# PatchPanel.net
KiCad netlist of a schematic drawn in EAGLE
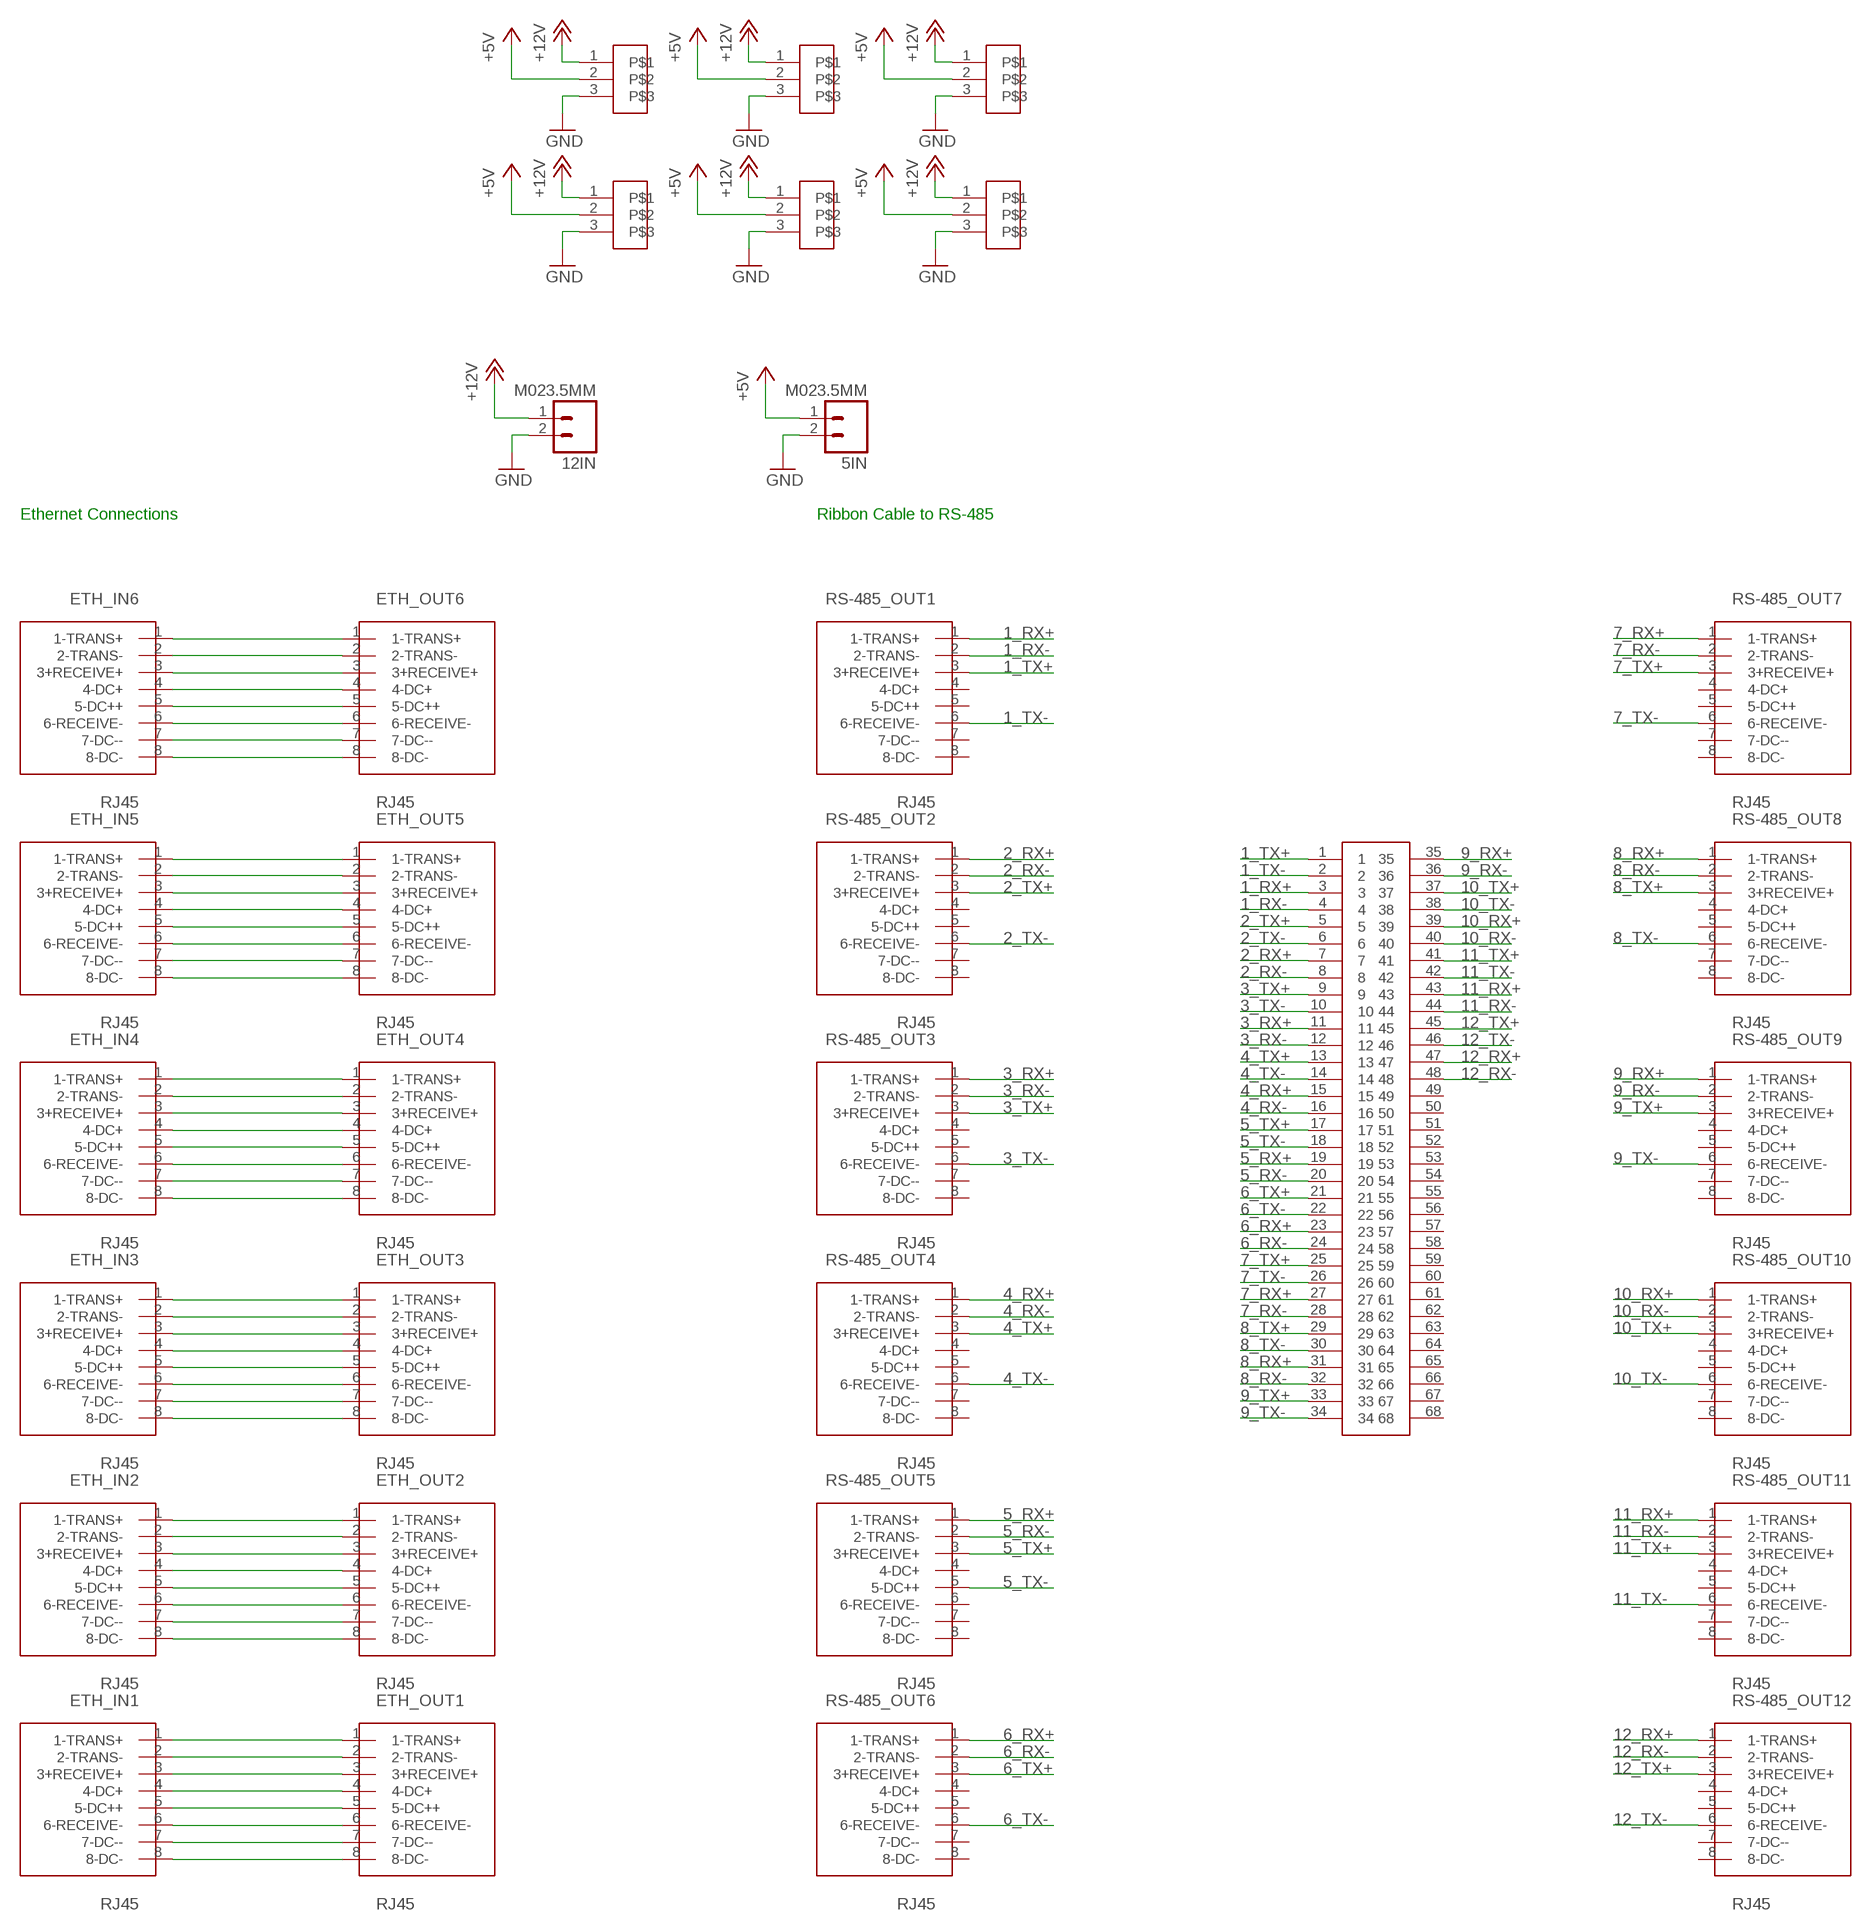
[diagram p0: schematic, sheet 1]

(export (version "E")
  (design (tool "Eeschema 10.0.6"))
  (components
    (comp (ref "5IN")
      (value "M023.5MM")
      (footprint "eagle-import:SCREWTERMINAL-3.5MM-2")
      (libsource (lib "eagle-import") (part "M023.5MM"))
    )
    (comp (ref "12IN")
      (value "M023.5MM")
      (footprint "eagle-import:SCREWTERMINAL-3.5MM-2")
      (libsource (lib "eagle-import") (part "M023.5MM"))
    )
    (comp (ref "ETH_IN1")
      (value "RJ45")
      (footprint "eagle-import:RJ45-CAT5E")
      (libsource (lib "eagle-import") (part "RJ45"))
    )
    (comp (ref "ETH_IN2")
      (value "RJ45")
      (footprint "eagle-import:RJ45-CAT5E")
      (libsource (lib "eagle-import") (part "RJ45"))
    )
    (comp (ref "ETH_IN3")
      (value "RJ45")
      (footprint "eagle-import:RJ45-CAT5E")
      (libsource (lib "eagle-import") (part "RJ45"))
    )
    (comp (ref "ETH_IN4")
      (value "RJ45")
      (footprint "eagle-import:RJ45-CAT5E")
      (libsource (lib "eagle-import") (part "RJ45"))
    )
    (comp (ref "ETH_IN5")
      (value "RJ45")
      (footprint "eagle-import:RJ45-CAT5E")
      (libsource (lib "eagle-import") (part "RJ45"))
    )
    (comp (ref "ETH_IN6")
      (value "RJ45")
      (footprint "eagle-import:RJ45-CAT5E")
      (libsource (lib "eagle-import") (part "RJ45"))
    )
    (comp (ref "ETH_OUT1")
      (value "RJ45")
      (footprint "eagle-import:RJ45-CAT5E")
      (libsource (lib "eagle-import") (part "RJ45"))
    )
    (comp (ref "ETH_OUT2")
      (value "RJ45")
      (footprint "eagle-import:RJ45-CAT5E")
      (libsource (lib "eagle-import") (part "RJ45"))
    )
    (comp (ref "ETH_OUT3")
      (value "RJ45")
      (footprint "eagle-import:RJ45-CAT5E")
      (libsource (lib "eagle-import") (part "RJ45"))
    )
    (comp (ref "ETH_OUT4")
      (value "RJ45")
      (footprint "eagle-import:RJ45-CAT5E")
      (libsource (lib "eagle-import") (part "RJ45"))
    )
    (comp (ref "ETH_OUT5")
      (value "RJ45")
      (footprint "eagle-import:RJ45-CAT5E")
      (libsource (lib "eagle-import") (part "RJ45"))
    )
    (comp (ref "ETH_OUT6")
      (value "RJ45")
      (footprint "eagle-import:RJ45-CAT5E")
      (libsource (lib "eagle-import") (part "RJ45"))
    )
    (comp (ref "RS-485_OUT1")
      (value "RJ45")
      (footprint "eagle-import:RJ45-CAT5E")
      (libsource (lib "eagle-import") (part "RJ45"))
    )
    (comp (ref "RS-485_OUT2")
      (value "RJ45")
      (footprint "eagle-import:RJ45-CAT5E")
      (libsource (lib "eagle-import") (part "RJ45"))
    )
    (comp (ref "RS-485_OUT3")
      (value "RJ45")
      (footprint "eagle-import:RJ45-CAT5E")
      (libsource (lib "eagle-import") (part "RJ45"))
    )
    (comp (ref "RS-485_OUT4")
      (value "RJ45")
      (footprint "eagle-import:RJ45-CAT5E")
      (libsource (lib "eagle-import") (part "RJ45"))
    )
    (comp (ref "RS-485_OUT5")
      (value "RJ45")
      (footprint "eagle-import:RJ45-CAT5E")
      (libsource (lib "eagle-import") (part "RJ45"))
    )
    (comp (ref "RS-485_OUT6")
      (value "RJ45")
      (footprint "eagle-import:RJ45-CAT5E")
      (libsource (lib "eagle-import") (part "RJ45"))
    )
    (comp (ref "RS-485_OUT7")
      (value "RJ45")
      (footprint "eagle-import:RJ45-CAT5E")
      (libsource (lib "eagle-import") (part "RJ45"))
    )
    (comp (ref "RS-485_OUT8")
      (value "RJ45")
      (footprint "eagle-import:RJ45-CAT5E")
      (libsource (lib "eagle-import") (part "RJ45"))
    )
    (comp (ref "RS-485_OUT9")
      (value "RJ45")
      (footprint "eagle-import:RJ45-CAT5E")
      (libsource (lib "eagle-import") (part "RJ45"))
    )
    (comp (ref "RS-485_OUT10")
      (value "RJ45")
      (footprint "eagle-import:RJ45-CAT5E")
      (libsource (lib "eagle-import") (part "RJ45"))
    )
    (comp (ref "RS-485_OUT11")
      (value "RJ45")
      (footprint "eagle-import:RJ45-CAT5E")
      (libsource (lib "eagle-import") (part "RJ45"))
    )
    (comp (ref "RS-485_OUT12")
      (value "RJ45")
      (footprint "eagle-import:RJ45-CAT5E")
      (libsource (lib "eagle-import") (part "RJ45"))
    )
    (comp (ref "U$1")
      (value "TB60050685100")
      (footprint "eagle-import:60050685100")
      (libsource (lib "eagle-import") (part "TB60050685100"))
    )
    (comp (ref "U$2")
      (value "3PIN")
      (footprint "eagle-import:0.93_")
      (libsource (lib "eagle-import") (part "3PIN"))
    )
    (comp (ref "U$3")
      (value "3PIN")
      (footprint "eagle-import:0.93_")
      (libsource (lib "eagle-import") (part "3PIN"))
    )
    (comp (ref "U$4")
      (value "3PIN")
      (footprint "eagle-import:0.93_")
      (libsource (lib "eagle-import") (part "3PIN"))
    )
    (comp (ref "U$5")
      (value "3PIN")
      (footprint "eagle-import:0.93_")
      (libsource (lib "eagle-import") (part "3PIN"))
    )
    (comp (ref "U$6")
      (value "3PIN")
      (footprint "eagle-import:0.93_")
      (libsource (lib "eagle-import") (part "3PIN"))
    )
    (comp (ref "U$7")
      (value "3PIN")
      (footprint "eagle-import:0.93_")
      (libsource (lib "eagle-import") (part "3PIN"))
    )
  )
  (nets
    (net (code "1") (name "+5V") (class "Default")
      (node (ref "5IN") (pin "1") (pinfunction "1_1") (pintype "passive"))
      (node (ref "U$2") (pin "2") (pinfunction "P$2_2") (pintype "bidirectional"))
      (node (ref "U$3") (pin "2") (pinfunction "P$2_2") (pintype "bidirectional"))
      (node (ref "U$4") (pin "2") (pinfunction "P$2_2") (pintype "bidirectional"))
      (node (ref "U$5") (pin "2") (pinfunction "P$2_2") (pintype "bidirectional"))
      (node (ref "U$6") (pin "2") (pinfunction "P$2_2") (pintype "bidirectional"))
      (node (ref "U$7") (pin "2") (pinfunction "P$2_2") (pintype "bidirectional"))
    )
    (net (code "2") (name "+12V") (class "Default")
      (node (ref "12IN") (pin "1") (pinfunction "1_1") (pintype "passive"))
      (node (ref "U$2") (pin "1") (pinfunction "P$1_1") (pintype "bidirectional"))
      (node (ref "U$3") (pin "1") (pinfunction "P$1_1") (pintype "bidirectional"))
      (node (ref "U$4") (pin "1") (pinfunction "P$1_1") (pintype "bidirectional"))
      (node (ref "U$5") (pin "1") (pinfunction "P$1_1") (pintype "bidirectional"))
      (node (ref "U$6") (pin "1") (pinfunction "P$1_1") (pintype "bidirectional"))
      (node (ref "U$7") (pin "1") (pinfunction "P$1_1") (pintype "bidirectional"))
    )
    (net (code "3") (name "/1_RX+") (class "Default")
      (node (ref "RS-485_OUT1") (pin "1") (pinfunction "1-TRANS+_1") (pintype "bidirectional"))
      (node (ref "U$1") (pin "3") (pinfunction "3_3") (pintype "bidirectional"))
    )
    (net (code "4") (name "/1_RX-") (class "Default")
      (node (ref "RS-485_OUT1") (pin "2") (pinfunction "2-TRANS-_2") (pintype "bidirectional"))
      (node (ref "U$1") (pin "4") (pinfunction "4_4") (pintype "bidirectional"))
    )
    (net (code "5") (name "/1_TX+") (class "Default")
      (node (ref "RS-485_OUT1") (pin "3") (pinfunction "3+RECEIVE+_3") (pintype "bidirectional"))
      (node (ref "U$1") (pin "1") (pinfunction "1_1") (pintype "bidirectional"))
    )
    (net (code "6") (name "/1_TX-") (class "Default")
      (node (ref "RS-485_OUT1") (pin "6") (pinfunction "6-RECEIVE-_6") (pintype "bidirectional"))
      (node (ref "U$1") (pin "2") (pinfunction "2_2") (pintype "bidirectional"))
    )
    (net (code "7") (name "/2_RX+") (class "Default")
      (node (ref "RS-485_OUT2") (pin "1") (pinfunction "1-TRANS+_1") (pintype "bidirectional"))
      (node (ref "U$1") (pin "7") (pinfunction "7_7") (pintype "bidirectional"))
    )
    (net (code "8") (name "/2_RX-") (class "Default")
      (node (ref "RS-485_OUT2") (pin "2") (pinfunction "2-TRANS-_2") (pintype "bidirectional"))
      (node (ref "U$1") (pin "8") (pinfunction "8_8") (pintype "bidirectional"))
    )
    (net (code "9") (name "/2_TX+") (class "Default")
      (node (ref "RS-485_OUT2") (pin "3") (pinfunction "3+RECEIVE+_3") (pintype "bidirectional"))
      (node (ref "U$1") (pin "5") (pinfunction "5_5") (pintype "bidirectional"))
    )
    (net (code "10") (name "/2_TX-") (class "Default")
      (node (ref "RS-485_OUT2") (pin "6") (pinfunction "6-RECEIVE-_6") (pintype "bidirectional"))
      (node (ref "U$1") (pin "6") (pinfunction "6_6") (pintype "bidirectional"))
    )
    (net (code "11") (name "/3_RX+") (class "Default")
      (node (ref "RS-485_OUT3") (pin "1") (pinfunction "1-TRANS+_1") (pintype "bidirectional"))
      (node (ref "U$1") (pin "11") (pinfunction "11_11") (pintype "bidirectional"))
    )
    (net (code "12") (name "/3_RX-") (class "Default")
      (node (ref "RS-485_OUT3") (pin "2") (pinfunction "2-TRANS-_2") (pintype "bidirectional"))
      (node (ref "U$1") (pin "12") (pinfunction "12_12") (pintype "bidirectional"))
    )
    (net (code "13") (name "/3_TX+") (class "Default")
      (node (ref "RS-485_OUT3") (pin "3") (pinfunction "3+RECEIVE+_3") (pintype "bidirectional"))
      (node (ref "U$1") (pin "9") (pinfunction "9_9") (pintype "bidirectional"))
    )
    (net (code "14") (name "/3_TX-") (class "Default")
      (node (ref "RS-485_OUT3") (pin "6") (pinfunction "6-RECEIVE-_6") (pintype "bidirectional"))
      (node (ref "U$1") (pin "10") (pinfunction "10_10") (pintype "bidirectional"))
    )
    (net (code "15") (name "/4_RX+") (class "Default")
      (node (ref "RS-485_OUT4") (pin "1") (pinfunction "1-TRANS+_1") (pintype "bidirectional"))
      (node (ref "U$1") (pin "15") (pinfunction "15_15") (pintype "bidirectional"))
    )
    (net (code "16") (name "/4_RX-") (class "Default")
      (node (ref "RS-485_OUT4") (pin "2") (pinfunction "2-TRANS-_2") (pintype "bidirectional"))
      (node (ref "U$1") (pin "16") (pinfunction "16_16") (pintype "bidirectional"))
    )
    (net (code "17") (name "/4_TX+") (class "Default")
      (node (ref "RS-485_OUT4") (pin "3") (pinfunction "3+RECEIVE+_3") (pintype "bidirectional"))
      (node (ref "U$1") (pin "13") (pinfunction "13_13") (pintype "bidirectional"))
    )
    (net (code "18") (name "/4_TX-") (class "Default")
      (node (ref "RS-485_OUT4") (pin "6") (pinfunction "6-RECEIVE-_6") (pintype "bidirectional"))
      (node (ref "U$1") (pin "14") (pinfunction "14_14") (pintype "bidirectional"))
    )
    (net (code "19") (name "/5_RX+") (class "Default")
      (node (ref "RS-485_OUT5") (pin "1") (pinfunction "1-TRANS+_1") (pintype "bidirectional"))
      (node (ref "U$1") (pin "19") (pinfunction "19_19") (pintype "bidirectional"))
    )
    (net (code "20") (name "/5_RX-") (class "Default")
      (node (ref "RS-485_OUT5") (pin "2") (pinfunction "2-TRANS-_2") (pintype "bidirectional"))
      (node (ref "U$1") (pin "20") (pinfunction "20_20") (pintype "bidirectional"))
    )
    (net (code "21") (name "/5_TX+") (class "Default")
      (node (ref "RS-485_OUT5") (pin "3") (pinfunction "3+RECEIVE+_3") (pintype "bidirectional"))
      (node (ref "U$1") (pin "17") (pinfunction "17_17") (pintype "bidirectional"))
    )
    (net (code "22") (name "/5_TX-") (class "Default")
      (node (ref "RS-485_OUT5") (pin "5") (pinfunction "5-DC++_5") (pintype "bidirectional"))
      (node (ref "U$1") (pin "18") (pinfunction "18_18") (pintype "bidirectional"))
    )
    (net (code "23") (name "/6_RX+") (class "Default")
      (node (ref "RS-485_OUT6") (pin "1") (pinfunction "1-TRANS+_1") (pintype "bidirectional"))
      (node (ref "U$1") (pin "23") (pinfunction "23_23") (pintype "bidirectional"))
    )
    (net (code "24") (name "/6_RX-") (class "Default")
      (node (ref "RS-485_OUT6") (pin "2") (pinfunction "2-TRANS-_2") (pintype "bidirectional"))
      (node (ref "U$1") (pin "24") (pinfunction "24_24") (pintype "bidirectional"))
    )
    (net (code "25") (name "/6_TX+") (class "Default")
      (node (ref "RS-485_OUT6") (pin "3") (pinfunction "3+RECEIVE+_3") (pintype "bidirectional"))
      (node (ref "U$1") (pin "21") (pinfunction "21_21") (pintype "bidirectional"))
    )
    (net (code "26") (name "/6_TX-") (class "Default")
      (node (ref "RS-485_OUT6") (pin "6") (pinfunction "6-RECEIVE-_6") (pintype "bidirectional"))
      (node (ref "U$1") (pin "22") (pinfunction "22_22") (pintype "bidirectional"))
    )
    (net (code "27") (name "/7_RX+") (class "Default")
      (node (ref "RS-485_OUT7") (pin "1") (pinfunction "1-TRANS+_1") (pintype "bidirectional"))
      (node (ref "U$1") (pin "27") (pinfunction "27_27") (pintype "bidirectional"))
    )
    (net (code "28") (name "/7_RX-") (class "Default")
      (node (ref "RS-485_OUT7") (pin "2") (pinfunction "2-TRANS-_2") (pintype "bidirectional"))
      (node (ref "U$1") (pin "28") (pinfunction "28_28") (pintype "bidirectional"))
    )
    (net (code "29") (name "/7_TX+") (class "Default")
      (node (ref "RS-485_OUT7") (pin "3") (pinfunction "3+RECEIVE+_3") (pintype "bidirectional"))
      (node (ref "U$1") (pin "25") (pinfunction "25_25") (pintype "bidirectional"))
    )
    (net (code "30") (name "/7_TX-") (class "Default")
      (node (ref "RS-485_OUT7") (pin "6") (pinfunction "6-RECEIVE-_6") (pintype "bidirectional"))
      (node (ref "U$1") (pin "26") (pinfunction "26_26") (pintype "bidirectional"))
    )
    (net (code "31") (name "/8_RX+") (class "Default")
      (node (ref "RS-485_OUT8") (pin "1") (pinfunction "1-TRANS+_1") (pintype "bidirectional"))
      (node (ref "U$1") (pin "31") (pinfunction "31_31") (pintype "bidirectional"))
    )
    (net (code "32") (name "/8_RX-") (class "Default")
      (node (ref "RS-485_OUT8") (pin "2") (pinfunction "2-TRANS-_2") (pintype "bidirectional"))
      (node (ref "U$1") (pin "32") (pinfunction "32_32") (pintype "bidirectional"))
    )
    (net (code "33") (name "/8_TX+") (class "Default")
      (node (ref "RS-485_OUT8") (pin "3") (pinfunction "3+RECEIVE+_3") (pintype "bidirectional"))
      (node (ref "U$1") (pin "29") (pinfunction "29_29") (pintype "bidirectional"))
    )
    (net (code "34") (name "/8_TX-") (class "Default")
      (node (ref "RS-485_OUT8") (pin "6") (pinfunction "6-RECEIVE-_6") (pintype "bidirectional"))
      (node (ref "U$1") (pin "30") (pinfunction "30_30") (pintype "bidirectional"))
    )
    (net (code "35") (name "/9_RX+") (class "Default")
      (node (ref "RS-485_OUT9") (pin "1") (pinfunction "1-TRANS+_1") (pintype "bidirectional"))
      (node (ref "U$1") (pin "35") (pinfunction "35_35") (pintype "bidirectional"))
    )
    (net (code "36") (name "/9_RX-") (class "Default")
      (node (ref "RS-485_OUT9") (pin "2") (pinfunction "2-TRANS-_2") (pintype "bidirectional"))
      (node (ref "U$1") (pin "36") (pinfunction "36_36") (pintype "bidirectional"))
    )
    (net (code "37") (name "/9_TX+") (class "Default")
      (node (ref "RS-485_OUT9") (pin "3") (pinfunction "3+RECEIVE+_3") (pintype "bidirectional"))
      (node (ref "U$1") (pin "33") (pinfunction "33_33") (pintype "bidirectional"))
    )
    (net (code "38") (name "/9_TX-") (class "Default")
      (node (ref "RS-485_OUT9") (pin "6") (pinfunction "6-RECEIVE-_6") (pintype "bidirectional"))
      (node (ref "U$1") (pin "34") (pinfunction "34_34") (pintype "bidirectional"))
    )
    (net (code "39") (name "/10_RX+") (class "Default")
      (node (ref "RS-485_OUT10") (pin "1") (pinfunction "1-TRANS+_1") (pintype "bidirectional"))
      (node (ref "U$1") (pin "39") (pinfunction "39_39") (pintype "bidirectional"))
    )
    (net (code "40") (name "/10_RX-") (class "Default")
      (node (ref "RS-485_OUT10") (pin "2") (pinfunction "2-TRANS-_2") (pintype "bidirectional"))
      (node (ref "U$1") (pin "40") (pinfunction "40_40") (pintype "bidirectional"))
    )
    (net (code "41") (name "/10_TX+") (class "Default")
      (node (ref "RS-485_OUT10") (pin "3") (pinfunction "3+RECEIVE+_3") (pintype "bidirectional"))
      (node (ref "U$1") (pin "37") (pinfunction "37_37") (pintype "bidirectional"))
    )
    (net (code "42") (name "/10_TX-") (class "Default")
      (node (ref "RS-485_OUT10") (pin "6") (pinfunction "6-RECEIVE-_6") (pintype "bidirectional"))
      (node (ref "U$1") (pin "38") (pinfunction "38_38") (pintype "bidirectional"))
    )
    (net (code "43") (name "/11_RX+") (class "Default")
      (node (ref "RS-485_OUT11") (pin "1") (pinfunction "1-TRANS+_1") (pintype "bidirectional"))
      (node (ref "U$1") (pin "43") (pinfunction "43_43") (pintype "bidirectional"))
    )
    (net (code "44") (name "/11_RX-") (class "Default")
      (node (ref "RS-485_OUT11") (pin "2") (pinfunction "2-TRANS-_2") (pintype "bidirectional"))
      (node (ref "U$1") (pin "44") (pinfunction "44_44") (pintype "bidirectional"))
    )
    (net (code "45") (name "/11_TX+") (class "Default")
      (node (ref "RS-485_OUT11") (pin "3") (pinfunction "3+RECEIVE+_3") (pintype "bidirectional"))
      (node (ref "U$1") (pin "41") (pinfunction "41_41") (pintype "bidirectional"))
    )
    (net (code "46") (name "/11_TX-") (class "Default")
      (node (ref "RS-485_OUT11") (pin "6") (pinfunction "6-RECEIVE-_6") (pintype "bidirectional"))
      (node (ref "U$1") (pin "42") (pinfunction "42_42") (pintype "bidirectional"))
    )
    (net (code "47") (name "/12_RX+") (class "Default")
      (node (ref "RS-485_OUT12") (pin "1") (pinfunction "1-TRANS+_1") (pintype "bidirectional"))
      (node (ref "U$1") (pin "47") (pinfunction "47_47") (pintype "bidirectional"))
    )
    (net (code "48") (name "/12_RX-") (class "Default")
      (node (ref "RS-485_OUT12") (pin "2") (pinfunction "2-TRANS-_2") (pintype "bidirectional"))
      (node (ref "U$1") (pin "48") (pinfunction "48_48") (pintype "bidirectional"))
    )
    (net (code "49") (name "/12_TX+") (class "Default")
      (node (ref "RS-485_OUT12") (pin "3") (pinfunction "3+RECEIVE+_3") (pintype "bidirectional"))
      (node (ref "U$1") (pin "45") (pinfunction "45_45") (pintype "bidirectional"))
    )
    (net (code "50") (name "/12_TX-") (class "Default")
      (node (ref "RS-485_OUT12") (pin "6") (pinfunction "6-RECEIVE-_6") (pintype "bidirectional"))
      (node (ref "U$1") (pin "46") (pinfunction "46_46") (pintype "bidirectional"))
    )
    (net (code "51") (name "GND") (class "Default")
      (node (ref "12IN") (pin "2") (pinfunction "2_2") (pintype "passive"))
      (node (ref "5IN") (pin "2") (pinfunction "2_2") (pintype "passive"))
      (node (ref "U$2") (pin "3") (pinfunction "P$3_3") (pintype "bidirectional"))
      (node (ref "U$3") (pin "3") (pinfunction "P$3_3") (pintype "bidirectional"))
      (node (ref "U$4") (pin "3") (pinfunction "P$3_3") (pintype "bidirectional"))
      (node (ref "U$5") (pin "3") (pinfunction "P$3_3") (pintype "bidirectional"))
      (node (ref "U$6") (pin "3") (pinfunction "P$3_3") (pintype "bidirectional"))
      (node (ref "U$7") (pin "3") (pinfunction "P$3_3") (pintype "bidirectional"))
    )
    (net (code "52") (name "Net-(ETH_IN1-1-TRANS+)") (class "Default")
      (node (ref "ETH_IN1") (pin "1") (pinfunction "1-TRANS+_1") (pintype "bidirectional"))
      (node (ref "ETH_OUT1") (pin "1") (pinfunction "1-TRANS+_1") (pintype "bidirectional"))
    )
    (net (code "53") (name "Net-(ETH_IN1-2-TRANS-)") (class "Default")
      (node (ref "ETH_IN1") (pin "2") (pinfunction "2-TRANS-_2") (pintype "bidirectional"))
      (node (ref "ETH_OUT1") (pin "2") (pinfunction "2-TRANS-_2") (pintype "bidirectional"))
    )
    (net (code "54") (name "Net-(ETH_IN1-3+RECEIVE+)") (class "Default")
      (node (ref "ETH_IN1") (pin "3") (pinfunction "3+RECEIVE+_3") (pintype "bidirectional"))
      (node (ref "ETH_OUT1") (pin "3") (pinfunction "3+RECEIVE+_3") (pintype "bidirectional"))
    )
    (net (code "55") (name "Net-(ETH_IN1-4-DC+)") (class "Default")
      (node (ref "ETH_IN1") (pin "4") (pinfunction "4-DC+_4") (pintype "bidirectional"))
      (node (ref "ETH_OUT1") (pin "4") (pinfunction "4-DC+_4") (pintype "bidirectional"))
    )
    (net (code "56") (name "Net-(ETH_IN1-5-DC++)") (class "Default")
      (node (ref "ETH_IN1") (pin "5") (pinfunction "5-DC++_5") (pintype "bidirectional"))
      (node (ref "ETH_OUT1") (pin "5") (pinfunction "5-DC++_5") (pintype "bidirectional"))
    )
    (net (code "57") (name "Net-(ETH_IN1-6-RECEIVE-)") (class "Default")
      (node (ref "ETH_IN1") (pin "6") (pinfunction "6-RECEIVE-_6") (pintype "bidirectional"))
      (node (ref "ETH_OUT1") (pin "6") (pinfunction "6-RECEIVE-_6") (pintype "bidirectional"))
    )
    (net (code "58") (name "Net-(ETH_IN1-7-DC--)") (class "Default")
      (node (ref "ETH_IN1") (pin "7") (pinfunction "7-DC--_7") (pintype "bidirectional"))
      (node (ref "ETH_OUT1") (pin "7") (pinfunction "7-DC--_7") (pintype "bidirectional"))
    )
    (net (code "59") (name "Net-(ETH_IN1-8-DC-)") (class "Default")
      (node (ref "ETH_IN1") (pin "8") (pinfunction "8-DC-_8") (pintype "bidirectional"))
      (node (ref "ETH_OUT1") (pin "8") (pinfunction "8-DC-_8") (pintype "bidirectional"))
    )
    (net (code "60") (name "Net-(ETH_IN2-1-TRANS+)") (class "Default")
      (node (ref "ETH_IN2") (pin "1") (pinfunction "1-TRANS+_1") (pintype "bidirectional"))
      (node (ref "ETH_OUT2") (pin "1") (pinfunction "1-TRANS+_1") (pintype "bidirectional"))
    )
    (net (code "61") (name "Net-(ETH_IN2-2-TRANS-)") (class "Default")
      (node (ref "ETH_IN2") (pin "2") (pinfunction "2-TRANS-_2") (pintype "bidirectional"))
      (node (ref "ETH_OUT2") (pin "2") (pinfunction "2-TRANS-_2") (pintype "bidirectional"))
    )
    (net (code "62") (name "Net-(ETH_IN2-3+RECEIVE+)") (class "Default")
      (node (ref "ETH_IN2") (pin "3") (pinfunction "3+RECEIVE+_3") (pintype "bidirectional"))
      (node (ref "ETH_OUT2") (pin "3") (pinfunction "3+RECEIVE+_3") (pintype "bidirectional"))
    )
    (net (code "63") (name "Net-(ETH_IN2-4-DC+)") (class "Default")
      (node (ref "ETH_IN2") (pin "4") (pinfunction "4-DC+_4") (pintype "bidirectional"))
      (node (ref "ETH_OUT2") (pin "4") (pinfunction "4-DC+_4") (pintype "bidirectional"))
    )
    (net (code "64") (name "Net-(ETH_IN2-5-DC++)") (class "Default")
      (node (ref "ETH_IN2") (pin "5") (pinfunction "5-DC++_5") (pintype "bidirectional"))
      (node (ref "ETH_OUT2") (pin "5") (pinfunction "5-DC++_5") (pintype "bidirectional"))
    )
    (net (code "65") (name "Net-(ETH_IN2-6-RECEIVE-)") (class "Default")
      (node (ref "ETH_IN2") (pin "6") (pinfunction "6-RECEIVE-_6") (pintype "bidirectional"))
      (node (ref "ETH_OUT2") (pin "6") (pinfunction "6-RECEIVE-_6") (pintype "bidirectional"))
    )
    (net (code "66") (name "Net-(ETH_IN2-7-DC--)") (class "Default")
      (node (ref "ETH_IN2") (pin "7") (pinfunction "7-DC--_7") (pintype "bidirectional"))
      (node (ref "ETH_OUT2") (pin "7") (pinfunction "7-DC--_7") (pintype "bidirectional"))
    )
    (net (code "67") (name "Net-(ETH_IN2-8-DC-)") (class "Default")
      (node (ref "ETH_IN2") (pin "8") (pinfunction "8-DC-_8") (pintype "bidirectional"))
      (node (ref "ETH_OUT2") (pin "8") (pinfunction "8-DC-_8") (pintype "bidirectional"))
    )
    (net (code "68") (name "Net-(ETH_IN3-1-TRANS+)") (class "Default")
      (node (ref "ETH_IN3") (pin "1") (pinfunction "1-TRANS+_1") (pintype "bidirectional"))
      (node (ref "ETH_OUT3") (pin "1") (pinfunction "1-TRANS+_1") (pintype "bidirectional"))
    )
    (net (code "69") (name "Net-(ETH_IN3-2-TRANS-)") (class "Default")
      (node (ref "ETH_IN3") (pin "2") (pinfunction "2-TRANS-_2") (pintype "bidirectional"))
      (node (ref "ETH_OUT3") (pin "2") (pinfunction "2-TRANS-_2") (pintype "bidirectional"))
    )
    (net (code "70") (name "Net-(ETH_IN3-3+RECEIVE+)") (class "Default")
      (node (ref "ETH_IN3") (pin "3") (pinfunction "3+RECEIVE+_3") (pintype "bidirectional"))
      (node (ref "ETH_OUT3") (pin "3") (pinfunction "3+RECEIVE+_3") (pintype "bidirectional"))
    )
    (net (code "71") (name "Net-(ETH_IN3-4-DC+)") (class "Default")
      (node (ref "ETH_IN3") (pin "4") (pinfunction "4-DC+_4") (pintype "bidirectional"))
      (node (ref "ETH_OUT3") (pin "4") (pinfunction "4-DC+_4") (pintype "bidirectional"))
    )
    (net (code "72") (name "Net-(ETH_IN3-5-DC++)") (class "Default")
      (node (ref "ETH_IN3") (pin "5") (pinfunction "5-DC++_5") (pintype "bidirectional"))
      (node (ref "ETH_OUT3") (pin "5") (pinfunction "5-DC++_5") (pintype "bidirectional"))
    )
    (net (code "73") (name "Net-(ETH_IN3-6-RECEIVE-)") (class "Default")
      (node (ref "ETH_IN3") (pin "6") (pinfunction "6-RECEIVE-_6") (pintype "bidirectional"))
      (node (ref "ETH_OUT3") (pin "6") (pinfunction "6-RECEIVE-_6") (pintype "bidirectional"))
    )
    (net (code "74") (name "Net-(ETH_IN3-7-DC--)") (class "Default")
      (node (ref "ETH_IN3") (pin "7") (pinfunction "7-DC--_7") (pintype "bidirectional"))
      (node (ref "ETH_OUT3") (pin "7") (pinfunction "7-DC--_7") (pintype "bidirectional"))
    )
    (net (code "75") (name "Net-(ETH_IN3-8-DC-)") (class "Default")
      (node (ref "ETH_IN3") (pin "8") (pinfunction "8-DC-_8") (pintype "bidirectional"))
      (node (ref "ETH_OUT3") (pin "8") (pinfunction "8-DC-_8") (pintype "bidirectional"))
    )
    (net (code "76") (name "Net-(ETH_IN4-1-TRANS+)") (class "Default")
      (node (ref "ETH_IN4") (pin "1") (pinfunction "1-TRANS+_1") (pintype "bidirectional"))
      (node (ref "ETH_OUT4") (pin "1") (pinfunction "1-TRANS+_1") (pintype "bidirectional"))
    )
    (net (code "77") (name "Net-(ETH_IN4-2-TRANS-)") (class "Default")
      (node (ref "ETH_IN4") (pin "2") (pinfunction "2-TRANS-_2") (pintype "bidirectional"))
      (node (ref "ETH_OUT4") (pin "2") (pinfunction "2-TRANS-_2") (pintype "bidirectional"))
    )
    (net (code "78") (name "Net-(ETH_IN4-3+RECEIVE+)") (class "Default")
      (node (ref "ETH_IN4") (pin "3") (pinfunction "3+RECEIVE+_3") (pintype "bidirectional"))
      (node (ref "ETH_OUT4") (pin "3") (pinfunction "3+RECEIVE+_3") (pintype "bidirectional"))
    )
    (net (code "79") (name "Net-(ETH_IN4-4-DC+)") (class "Default")
      (node (ref "ETH_IN4") (pin "4") (pinfunction "4-DC+_4") (pintype "bidirectional"))
      (node (ref "ETH_OUT4") (pin "4") (pinfunction "4-DC+_4") (pintype "bidirectional"))
    )
    (net (code "80") (name "Net-(ETH_IN4-5-DC++)") (class "Default")
      (node (ref "ETH_IN4") (pin "5") (pinfunction "5-DC++_5") (pintype "bidirectional"))
      (node (ref "ETH_OUT4") (pin "5") (pinfunction "5-DC++_5") (pintype "bidirectional"))
    )
    (net (code "81") (name "Net-(ETH_IN4-6-RECEIVE-)") (class "Default")
      (node (ref "ETH_IN4") (pin "6") (pinfunction "6-RECEIVE-_6") (pintype "bidirectional"))
      (node (ref "ETH_OUT4") (pin "6") (pinfunction "6-RECEIVE-_6") (pintype "bidirectional"))
    )
    (net (code "82") (name "Net-(ETH_IN4-7-DC--)") (class "Default")
      (node (ref "ETH_IN4") (pin "7") (pinfunction "7-DC--_7") (pintype "bidirectional"))
      (node (ref "ETH_OUT4") (pin "7") (pinfunction "7-DC--_7") (pintype "bidirectional"))
    )
    (net (code "83") (name "Net-(ETH_IN4-8-DC-)") (class "Default")
      (node (ref "ETH_IN4") (pin "8") (pinfunction "8-DC-_8") (pintype "bidirectional"))
      (node (ref "ETH_OUT4") (pin "8") (pinfunction "8-DC-_8") (pintype "bidirectional"))
    )
    (net (code "84") (name "Net-(ETH_IN5-1-TRANS+)") (class "Default")
      (node (ref "ETH_IN5") (pin "1") (pinfunction "1-TRANS+_1") (pintype "bidirectional"))
      (node (ref "ETH_OUT5") (pin "1") (pinfunction "1-TRANS+_1") (pintype "bidirectional"))
    )
    (net (code "85") (name "Net-(ETH_IN5-2-TRANS-)") (class "Default")
      (node (ref "ETH_IN5") (pin "2") (pinfunction "2-TRANS-_2") (pintype "bidirectional"))
      (node (ref "ETH_OUT5") (pin "2") (pinfunction "2-TRANS-_2") (pintype "bidirectional"))
    )
    (net (code "86") (name "Net-(ETH_IN5-3+RECEIVE+)") (class "Default")
      (node (ref "ETH_IN5") (pin "3") (pinfunction "3+RECEIVE+_3") (pintype "bidirectional"))
      (node (ref "ETH_OUT5") (pin "3") (pinfunction "3+RECEIVE+_3") (pintype "bidirectional"))
    )
    (net (code "87") (name "Net-(ETH_IN5-4-DC+)") (class "Default")
      (node (ref "ETH_IN5") (pin "4") (pinfunction "4-DC+_4") (pintype "bidirectional"))
      (node (ref "ETH_OUT5") (pin "4") (pinfunction "4-DC+_4") (pintype "bidirectional"))
    )
    (net (code "88") (name "Net-(ETH_IN5-5-DC++)") (class "Default")
      (node (ref "ETH_IN5") (pin "5") (pinfunction "5-DC++_5") (pintype "bidirectional"))
      (node (ref "ETH_OUT5") (pin "5") (pinfunction "5-DC++_5") (pintype "bidirectional"))
    )
    (net (code "89") (name "Net-(ETH_IN5-6-RECEIVE-)") (class "Default")
      (node (ref "ETH_IN5") (pin "6") (pinfunction "6-RECEIVE-_6") (pintype "bidirectional"))
      (node (ref "ETH_OUT5") (pin "6") (pinfunction "6-RECEIVE-_6") (pintype "bidirectional"))
    )
    (net (code "90") (name "Net-(ETH_IN5-7-DC--)") (class "Default")
      (node (ref "ETH_IN5") (pin "7") (pinfunction "7-DC--_7") (pintype "bidirectional"))
      (node (ref "ETH_OUT5") (pin "7") (pinfunction "7-DC--_7") (pintype "bidirectional"))
    )
    (net (code "91") (name "Net-(ETH_IN5-8-DC-)") (class "Default")
      (node (ref "ETH_IN5") (pin "8") (pinfunction "8-DC-_8") (pintype "bidirectional"))
      (node (ref "ETH_OUT5") (pin "8") (pinfunction "8-DC-_8") (pintype "bidirectional"))
    )
    (net (code "92") (name "Net-(ETH_IN6-1-TRANS+)") (class "Default")
      (node (ref "ETH_IN6") (pin "1") (pinfunction "1-TRANS+_1") (pintype "bidirectional"))
      (node (ref "ETH_OUT6") (pin "1") (pinfunction "1-TRANS+_1") (pintype "bidirectional"))
    )
    (net (code "93") (name "Net-(ETH_IN6-2-TRANS-)") (class "Default")
      (node (ref "ETH_IN6") (pin "2") (pinfunction "2-TRANS-_2") (pintype "bidirectional"))
      (node (ref "ETH_OUT6") (pin "2") (pinfunction "2-TRANS-_2") (pintype "bidirectional"))
    )
    (net (code "94") (name "Net-(ETH_IN6-3+RECEIVE+)") (class "Default")
      (node (ref "ETH_IN6") (pin "3") (pinfunction "3+RECEIVE+_3") (pintype "bidirectional"))
      (node (ref "ETH_OUT6") (pin "3") (pinfunction "3+RECEIVE+_3") (pintype "bidirectional"))
    )
    (net (code "95") (name "Net-(ETH_IN6-4-DC+)") (class "Default")
      (node (ref "ETH_IN6") (pin "4") (pinfunction "4-DC+_4") (pintype "bidirectional"))
      (node (ref "ETH_OUT6") (pin "4") (pinfunction "4-DC+_4") (pintype "bidirectional"))
    )
    (net (code "96") (name "Net-(ETH_IN6-5-DC++)") (class "Default")
      (node (ref "ETH_IN6") (pin "5") (pinfunction "5-DC++_5") (pintype "bidirectional"))
      (node (ref "ETH_OUT6") (pin "5") (pinfunction "5-DC++_5") (pintype "bidirectional"))
    )
    (net (code "97") (name "Net-(ETH_IN6-6-RECEIVE-)") (class "Default")
      (node (ref "ETH_IN6") (pin "6") (pinfunction "6-RECEIVE-_6") (pintype "bidirectional"))
      (node (ref "ETH_OUT6") (pin "6") (pinfunction "6-RECEIVE-_6") (pintype "bidirectional"))
    )
    (net (code "98") (name "Net-(ETH_IN6-7-DC--)") (class "Default")
      (node (ref "ETH_IN6") (pin "7") (pinfunction "7-DC--_7") (pintype "bidirectional"))
      (node (ref "ETH_OUT6") (pin "7") (pinfunction "7-DC--_7") (pintype "bidirectional"))
    )
    (net (code "99") (name "Net-(ETH_IN6-8-DC-)") (class "Default")
      (node (ref "ETH_IN6") (pin "8") (pinfunction "8-DC-_8") (pintype "bidirectional"))
      (node (ref "ETH_OUT6") (pin "8") (pinfunction "8-DC-_8") (pintype "bidirectional"))
    )
    (net (code "100") (name "unconnected-(RS-485_OUT1-4-DC+-Pad4)") (class "Default")
      (node (ref "RS-485_OUT1") (pin "4") (pinfunction "4-DC+_4") (pintype "bidirectional"))
    )
    (net (code "101") (name "unconnected-(RS-485_OUT1-5-DC++-Pad5)") (class "Default")
      (node (ref "RS-485_OUT1") (pin "5") (pinfunction "5-DC++_5") (pintype "bidirectional"))
    )
    (net (code "102") (name "unconnected-(RS-485_OUT1-7-DC---Pad7)") (class "Default")
      (node (ref "RS-485_OUT1") (pin "7") (pinfunction "7-DC--_7") (pintype "bidirectional"))
    )
    (net (code "103") (name "unconnected-(RS-485_OUT1-8-DC--Pad8)") (class "Default")
      (node (ref "RS-485_OUT1") (pin "8") (pinfunction "8-DC-_8") (pintype "bidirectional"))
    )
    (net (code "104") (name "unconnected-(RS-485_OUT2-4-DC+-Pad4)") (class "Default")
      (node (ref "RS-485_OUT2") (pin "4") (pinfunction "4-DC+_4") (pintype "bidirectional"))
    )
    (net (code "105") (name "unconnected-(RS-485_OUT2-5-DC++-Pad5)") (class "Default")
      (node (ref "RS-485_OUT2") (pin "5") (pinfunction "5-DC++_5") (pintype "bidirectional"))
    )
    (net (code "106") (name "unconnected-(RS-485_OUT2-7-DC---Pad7)") (class "Default")
      (node (ref "RS-485_OUT2") (pin "7") (pinfunction "7-DC--_7") (pintype "bidirectional"))
    )
    (net (code "107") (name "unconnected-(RS-485_OUT2-8-DC--Pad8)") (class "Default")
      (node (ref "RS-485_OUT2") (pin "8") (pinfunction "8-DC-_8") (pintype "bidirectional"))
    )
    (net (code "108") (name "unconnected-(RS-485_OUT3-4-DC+-Pad4)") (class "Default")
      (node (ref "RS-485_OUT3") (pin "4") (pinfunction "4-DC+_4") (pintype "bidirectional"))
    )
    (net (code "109") (name "unconnected-(RS-485_OUT3-5-DC++-Pad5)") (class "Default")
      (node (ref "RS-485_OUT3") (pin "5") (pinfunction "5-DC++_5") (pintype "bidirectional"))
    )
    (net (code "110") (name "unconnected-(RS-485_OUT3-7-DC---Pad7)") (class "Default")
      (node (ref "RS-485_OUT3") (pin "7") (pinfunction "7-DC--_7") (pintype "bidirectional"))
    )
    (net (code "111") (name "unconnected-(RS-485_OUT3-8-DC--Pad8)") (class "Default")
      (node (ref "RS-485_OUT3") (pin "8") (pinfunction "8-DC-_8") (pintype "bidirectional"))
    )
    (net (code "112") (name "unconnected-(RS-485_OUT4-4-DC+-Pad4)") (class "Default")
      (node (ref "RS-485_OUT4") (pin "4") (pinfunction "4-DC+_4") (pintype "bidirectional"))
    )
    (net (code "113") (name "unconnected-(RS-485_OUT4-5-DC++-Pad5)") (class "Default")
      (node (ref "RS-485_OUT4") (pin "5") (pinfunction "5-DC++_5") (pintype "bidirectional"))
    )
    (net (code "114") (name "unconnected-(RS-485_OUT4-7-DC---Pad7)") (class "Default")
      (node (ref "RS-485_OUT4") (pin "7") (pinfunction "7-DC--_7") (pintype "bidirectional"))
    )
    (net (code "115") (name "unconnected-(RS-485_OUT4-8-DC--Pad8)") (class "Default")
      (node (ref "RS-485_OUT4") (pin "8") (pinfunction "8-DC-_8") (pintype "bidirectional"))
    )
    (net (code "116") (name "unconnected-(RS-485_OUT5-4-DC+-Pad4)") (class "Default")
      (node (ref "RS-485_OUT5") (pin "4") (pinfunction "4-DC+_4") (pintype "bidirectional"))
    )
    (net (code "117") (name "unconnected-(RS-485_OUT5-6-RECEIVE--Pad6)") (class "Default")
      (node (ref "RS-485_OUT5") (pin "6") (pinfunction "6-RECEIVE-_6") (pintype "bidirectional"))
    )
    (net (code "118") (name "unconnected-(RS-485_OUT5-7-DC---Pad7)") (class "Default")
      (node (ref "RS-485_OUT5") (pin "7") (pinfunction "7-DC--_7") (pintype "bidirectional"))
    )
    (net (code "119") (name "unconnected-(RS-485_OUT5-8-DC--Pad8)") (class "Default")
      (node (ref "RS-485_OUT5") (pin "8") (pinfunction "8-DC-_8") (pintype "bidirectional"))
    )
    (net (code "120") (name "unconnected-(RS-485_OUT6-4-DC+-Pad4)") (class "Default")
      (node (ref "RS-485_OUT6") (pin "4") (pinfunction "4-DC+_4") (pintype "bidirectional"))
    )
    (net (code "121") (name "unconnected-(RS-485_OUT6-5-DC++-Pad5)") (class "Default")
      (node (ref "RS-485_OUT6") (pin "5") (pinfunction "5-DC++_5") (pintype "bidirectional"))
    )
    (net (code "122") (name "unconnected-(RS-485_OUT6-7-DC---Pad7)") (class "Default")
      (node (ref "RS-485_OUT6") (pin "7") (pinfunction "7-DC--_7") (pintype "bidirectional"))
    )
    (net (code "123") (name "unconnected-(RS-485_OUT6-8-DC--Pad8)") (class "Default")
      (node (ref "RS-485_OUT6") (pin "8") (pinfunction "8-DC-_8") (pintype "bidirectional"))
    )
    (net (code "124") (name "unconnected-(RS-485_OUT7-4-DC+-Pad4)") (class "Default")
      (node (ref "RS-485_OUT7") (pin "4") (pinfunction "4-DC+_4") (pintype "bidirectional"))
    )
    (net (code "125") (name "unconnected-(RS-485_OUT7-5-DC++-Pad5)") (class "Default")
      (node (ref "RS-485_OUT7") (pin "5") (pinfunction "5-DC++_5") (pintype "bidirectional"))
    )
    (net (code "126") (name "unconnected-(RS-485_OUT7-7-DC---Pad7)") (class "Default")
      (node (ref "RS-485_OUT7") (pin "7") (pinfunction "7-DC--_7") (pintype "bidirectional"))
    )
    (net (code "127") (name "unconnected-(RS-485_OUT7-8-DC--Pad8)") (class "Default")
      (node (ref "RS-485_OUT7") (pin "8") (pinfunction "8-DC-_8") (pintype "bidirectional"))
    )
    (net (code "128") (name "unconnected-(RS-485_OUT8-4-DC+-Pad4)") (class "Default")
      (node (ref "RS-485_OUT8") (pin "4") (pinfunction "4-DC+_4") (pintype "bidirectional"))
    )
    (net (code "129") (name "unconnected-(RS-485_OUT8-5-DC++-Pad5)") (class "Default")
      (node (ref "RS-485_OUT8") (pin "5") (pinfunction "5-DC++_5") (pintype "bidirectional"))
    )
    (net (code "130") (name "unconnected-(RS-485_OUT8-7-DC---Pad7)") (class "Default")
      (node (ref "RS-485_OUT8") (pin "7") (pinfunction "7-DC--_7") (pintype "bidirectional"))
    )
    (net (code "131") (name "unconnected-(RS-485_OUT8-8-DC--Pad8)") (class "Default")
      (node (ref "RS-485_OUT8") (pin "8") (pinfunction "8-DC-_8") (pintype "bidirectional"))
    )
    (net (code "132") (name "unconnected-(RS-485_OUT9-4-DC+-Pad4)") (class "Default")
      (node (ref "RS-485_OUT9") (pin "4") (pinfunction "4-DC+_4") (pintype "bidirectional"))
    )
    (net (code "133") (name "unconnected-(RS-485_OUT9-5-DC++-Pad5)") (class "Default")
      (node (ref "RS-485_OUT9") (pin "5") (pinfunction "5-DC++_5") (pintype "bidirectional"))
    )
    (net (code "134") (name "unconnected-(RS-485_OUT9-7-DC---Pad7)") (class "Default")
      (node (ref "RS-485_OUT9") (pin "7") (pinfunction "7-DC--_7") (pintype "bidirectional"))
    )
    (net (code "135") (name "unconnected-(RS-485_OUT9-8-DC--Pad8)") (class "Default")
      (node (ref "RS-485_OUT9") (pin "8") (pinfunction "8-DC-_8") (pintype "bidirectional"))
    )
    (net (code "136") (name "unconnected-(RS-485_OUT10-4-DC+-Pad4)") (class "Default")
      (node (ref "RS-485_OUT10") (pin "4") (pinfunction "4-DC+_4") (pintype "bidirectional"))
    )
    (net (code "137") (name "unconnected-(RS-485_OUT10-5-DC++-Pad5)") (class "Default")
      (node (ref "RS-485_OUT10") (pin "5") (pinfunction "5-DC++_5") (pintype "bidirectional"))
    )
    (net (code "138") (name "unconnected-(RS-485_OUT10-7-DC---Pad7)") (class "Default")
      (node (ref "RS-485_OUT10") (pin "7") (pinfunction "7-DC--_7") (pintype "bidirectional"))
    )
    (net (code "139") (name "unconnected-(RS-485_OUT10-8-DC--Pad8)") (class "Default")
      (node (ref "RS-485_OUT10") (pin "8") (pinfunction "8-DC-_8") (pintype "bidirectional"))
    )
    (net (code "140") (name "unconnected-(RS-485_OUT11-4-DC+-Pad4)") (class "Default")
      (node (ref "RS-485_OUT11") (pin "4") (pinfunction "4-DC+_4") (pintype "bidirectional"))
    )
    (net (code "141") (name "unconnected-(RS-485_OUT11-5-DC++-Pad5)") (class "Default")
      (node (ref "RS-485_OUT11") (pin "5") (pinfunction "5-DC++_5") (pintype "bidirectional"))
    )
    (net (code "142") (name "unconnected-(RS-485_OUT11-7-DC---Pad7)") (class "Default")
      (node (ref "RS-485_OUT11") (pin "7") (pinfunction "7-DC--_7") (pintype "bidirectional"))
    )
    (net (code "143") (name "unconnected-(RS-485_OUT11-8-DC--Pad8)") (class "Default")
      (node (ref "RS-485_OUT11") (pin "8") (pinfunction "8-DC-_8") (pintype "bidirectional"))
    )
    (net (code "144") (name "unconnected-(RS-485_OUT12-4-DC+-Pad4)") (class "Default")
      (node (ref "RS-485_OUT12") (pin "4") (pinfunction "4-DC+_4") (pintype "bidirectional"))
    )
    (net (code "145") (name "unconnected-(RS-485_OUT12-5-DC++-Pad5)") (class "Default")
      (node (ref "RS-485_OUT12") (pin "5") (pinfunction "5-DC++_5") (pintype "bidirectional"))
    )
    (net (code "146") (name "unconnected-(RS-485_OUT12-7-DC---Pad7)") (class "Default")
      (node (ref "RS-485_OUT12") (pin "7") (pinfunction "7-DC--_7") (pintype "bidirectional"))
    )
    (net (code "147") (name "unconnected-(RS-485_OUT12-8-DC--Pad8)") (class "Default")
      (node (ref "RS-485_OUT12") (pin "8") (pinfunction "8-DC-_8") (pintype "bidirectional"))
    )
    (net (code "148") (name "unconnected-(U$1-Pad49)") (class "Default")
      (node (ref "U$1") (pin "49") (pinfunction "49_49") (pintype "bidirectional"))
    )
    (net (code "149") (name "unconnected-(U$1-Pad50)") (class "Default")
      (node (ref "U$1") (pin "50") (pinfunction "50_50") (pintype "bidirectional"))
    )
    (net (code "150") (name "unconnected-(U$1-Pad51)") (class "Default")
      (node (ref "U$1") (pin "51") (pinfunction "51_51") (pintype "bidirectional"))
    )
    (net (code "151") (name "unconnected-(U$1-Pad52)") (class "Default")
      (node (ref "U$1") (pin "52") (pinfunction "52_52") (pintype "bidirectional"))
    )
    (net (code "152") (name "unconnected-(U$1-Pad53)") (class "Default")
      (node (ref "U$1") (pin "53") (pinfunction "53_53") (pintype "bidirectional"))
    )
    (net (code "153") (name "unconnected-(U$1-Pad54)") (class "Default")
      (node (ref "U$1") (pin "54") (pinfunction "54_54") (pintype "bidirectional"))
    )
    (net (code "154") (name "unconnected-(U$1-Pad55)") (class "Default")
      (node (ref "U$1") (pin "55") (pinfunction "55_55") (pintype "bidirectional"))
    )
    (net (code "155") (name "unconnected-(U$1-Pad56)") (class "Default")
      (node (ref "U$1") (pin "56") (pinfunction "56_56") (pintype "bidirectional"))
    )
    (net (code "156") (name "unconnected-(U$1-Pad57)") (class "Default")
      (node (ref "U$1") (pin "57") (pinfunction "57_57") (pintype "bidirectional"))
    )
    (net (code "157") (name "unconnected-(U$1-Pad58)") (class "Default")
      (node (ref "U$1") (pin "58") (pinfunction "58_58") (pintype "bidirectional"))
    )
    (net (code "158") (name "unconnected-(U$1-Pad59)") (class "Default")
      (node (ref "U$1") (pin "59") (pinfunction "59_59") (pintype "bidirectional"))
    )
    (net (code "159") (name "unconnected-(U$1-Pad60)") (class "Default")
      (node (ref "U$1") (pin "60") (pinfunction "60_60") (pintype "bidirectional"))
    )
    (net (code "160") (name "unconnected-(U$1-Pad61)") (class "Default")
      (node (ref "U$1") (pin "61") (pinfunction "61_61") (pintype "bidirectional"))
    )
    (net (code "161") (name "unconnected-(U$1-Pad62)") (class "Default")
      (node (ref "U$1") (pin "62") (pinfunction "62_62") (pintype "bidirectional"))
    )
    (net (code "162") (name "unconnected-(U$1-Pad63)") (class "Default")
      (node (ref "U$1") (pin "63") (pinfunction "63_63") (pintype "bidirectional"))
    )
    (net (code "163") (name "unconnected-(U$1-Pad64)") (class "Default")
      (node (ref "U$1") (pin "64") (pinfunction "64_64") (pintype "bidirectional"))
    )
    (net (code "164") (name "unconnected-(U$1-Pad65)") (class "Default")
      (node (ref "U$1") (pin "65") (pinfunction "65_65") (pintype "bidirectional"))
    )
    (net (code "165") (name "unconnected-(U$1-Pad66)") (class "Default")
      (node (ref "U$1") (pin "66") (pinfunction "66_66") (pintype "bidirectional"))
    )
    (net (code "166") (name "unconnected-(U$1-Pad67)") (class "Default")
      (node (ref "U$1") (pin "67") (pinfunction "67_67") (pintype "bidirectional"))
    )
    (net (code "167") (name "unconnected-(U$1-Pad68)") (class "Default")
      (node (ref "U$1") (pin "68") (pinfunction "68_68") (pintype "bidirectional"))
    )
  )
)
